# Sheet1.net
KiCad netlist of a schematic drawn in Altium Designer
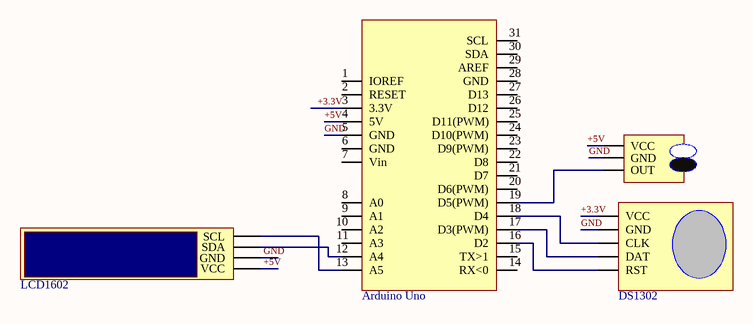
[diagram p0: Sheet1.SchDoc]

(export (version "E")
  (design (tool "Eeschema 10.0.6"))
  (components
    (comp (ref "Arduino") (value "Arduino Uno") (libsource (lib "Schlib1") (part "Arduino_C")))
    (comp (ref "LCD1602") (value "IIC1602") (libsource (lib "Schlib1") (part "IIC1602")))
    (comp (ref "rtc") (value "DS1302") (libsource (lib "Schlib1") (part "RTC时钟")))
    (comp (ref "红外避障") (value "红外避障1") (libsource (lib "Schlib1") (part "红外避障")))
  )
  (nets
    (net (code "1") (name "/+3.3V") (class "Default")
      (node (ref "Arduino") (pin "3") (pinfunction "3.3V_3") (pintype "passive"))
      (node (ref "rtc") (pin "241") (pinfunction "VCC_241") (pintype "passive"))
    )
    (net (code "2") (name "/+5V") (class "Default")
      (node (ref "Arduino") (pin "4") (pinfunction "5V_4") (pintype "passive"))
      (node (ref "LCD1602") (pin "192") (pinfunction "VCC_192") (pintype "passive"))
      (node (ref "红外避障") (pin "233") (pinfunction "VCC_233") (pintype "passive"))
    )
    (net (code "3") (name "/GND") (class "Default")
      (node (ref "Arduino") (pin "5") (pinfunction "GND_5") (pintype "passive"))
      (node (ref "LCD1602") (pin "193") (pinfunction "GND_193") (pintype "passive"))
      (node (ref "rtc") (pin "242") (pinfunction "GND_242") (pintype "passive"))
      (node (ref "红外避障") (pin "234") (pinfunction "GND_234") (pintype "passive"))
    )
    (net (code "4") (name "Net-(Arduino-A4)") (class "Default")
      (node (ref "Arduino") (pin "12") (pinfunction "A4_12") (pintype "passive"))
      (node (ref "LCD1602") (pin "194") (pinfunction "SDA_194") (pintype "passive"))
    )
    (net (code "5") (name "Net-(Arduino-A5)") (class "Default")
      (node (ref "Arduino") (pin "13") (pinfunction "A5_13") (pintype "passive"))
      (node (ref "LCD1602") (pin "195") (pinfunction "SCL_195") (pintype "passive"))
    )
    (net (code "6") (name "Net-(Arduino-D2)") (class "Default")
      (node (ref "Arduino") (pin "16") (pinfunction "D2_16") (pintype "passive"))
      (node (ref "rtc") (pin "245") (pinfunction "RST_245") (pintype "passive"))
    )
    (net (code "7") (name "Net-(Arduino-D3(PWM))") (class "Default")
      (node (ref "Arduino") (pin "17") (pinfunction "D3(PWM)_17") (pintype "passive"))
      (node (ref "rtc") (pin "244") (pinfunction "DAT_244") (pintype "passive"))
    )
    (net (code "8") (name "Net-(Arduino-D4)") (class "Default")
      (node (ref "Arduino") (pin "18") (pinfunction "D4_18") (pintype "passive"))
      (node (ref "rtc") (pin "243") (pinfunction "CLK_243") (pintype "passive"))
    )
    (net (code "9") (name "Net-(Arduino-D5(PWM))") (class "Default")
      (node (ref "Arduino") (pin "19") (pinfunction "D5(PWM)_19") (pintype "passive"))
      (node (ref "红外避障") (pin "235") (pinfunction "OUT_235") (pintype "passive"))
    )
    (net (code "10") (name "unconnected-(Arduino-A0-Pad8)") (class "Default")
      (node (ref "Arduino") (pin "8") (pinfunction "A0_8") (pintype "passive"))
    )
    (net (code "11") (name "unconnected-(Arduino-A1-Pad9)") (class "Default")
      (node (ref "Arduino") (pin "9") (pinfunction "A1_9") (pintype "passive"))
    )
    (net (code "12") (name "unconnected-(Arduino-A2-Pad10)") (class "Default")
      (node (ref "Arduino") (pin "10") (pinfunction "A2_10") (pintype "passive"))
    )
    (net (code "13") (name "unconnected-(Arduino-A3-Pad11)") (class "Default")
      (node (ref "Arduino") (pin "11") (pinfunction "A3_11") (pintype "passive"))
    )
    (net (code "14") (name "unconnected-(Arduino-AREF-Pad29)") (class "Default")
      (node (ref "Arduino") (pin "29") (pinfunction "AREF_29") (pintype "passive"))
    )
    (net (code "15") (name "unconnected-(Arduino-D6(PWM)-Pad20)") (class "Default")
      (node (ref "Arduino") (pin "20") (pinfunction "D6(PWM)_20") (pintype "passive"))
    )
    (net (code "16") (name "unconnected-(Arduino-D7-Pad21)") (class "Default")
      (node (ref "Arduino") (pin "21") (pinfunction "D7_21") (pintype "passive"))
    )
    (net (code "17") (name "unconnected-(Arduino-D8-Pad22)") (class "Default")
      (node (ref "Arduino") (pin "22") (pinfunction "D8_22") (pintype "passive"))
    )
    (net (code "18") (name "unconnected-(Arduino-D9(PWM)-Pad23)") (class "Default")
      (node (ref "Arduino") (pin "23") (pinfunction "D9(PWM)_23") (pintype "passive"))
    )
    (net (code "19") (name "unconnected-(Arduino-D10(PWM)-Pad24)") (class "Default")
      (node (ref "Arduino") (pin "24") (pinfunction "D10(PWM)_24") (pintype "passive"))
    )
    (net (code "20") (name "unconnected-(Arduino-D11(PWM)-Pad25)") (class "Default")
      (node (ref "Arduino") (pin "25") (pinfunction "D11(PWM)_25") (pintype "passive"))
    )
    (net (code "21") (name "unconnected-(Arduino-D12-Pad26)") (class "Default")
      (node (ref "Arduino") (pin "26") (pinfunction "D12_26") (pintype "passive"))
    )
    (net (code "22") (name "unconnected-(Arduino-D13-Pad27)") (class "Default")
      (node (ref "Arduino") (pin "27") (pinfunction "D13_27") (pintype "passive"))
    )
    (net (code "23") (name "unconnected-(Arduino-GND-Pad6)") (class "Default")
      (node (ref "Arduino") (pin "6") (pinfunction "GND_6") (pintype "passive"))
    )
    (net (code "24") (name "unconnected-(Arduino-GND-Pad28)") (class "Default")
      (node (ref "Arduino") (pin "28") (pinfunction "GND_28") (pintype "passive"))
    )
    (net (code "25") (name "unconnected-(Arduino-IOREF-Pad1)") (class "Default")
      (node (ref "Arduino") (pin "1") (pinfunction "IOREF_1") (pintype "passive"))
    )
    (net (code "26") (name "unconnected-(Arduino-RESET-Pad2)") (class "Default")
      (node (ref "Arduino") (pin "2") (pinfunction "RESET_2") (pintype "passive"))
    )
    (net (code "27") (name "unconnected-(Arduino-RX<0-Pad14)") (class "Default")
      (node (ref "Arduino") (pin "14") (pinfunction "RX<0_14") (pintype "passive"))
    )
    (net (code "28") (name "unconnected-(Arduino-SCL-Pad31)") (class "Default")
      (node (ref "Arduino") (pin "31") (pinfunction "SCL_31") (pintype "passive"))
    )
    (net (code "29") (name "unconnected-(Arduino-SDA-Pad30)") (class "Default")
      (node (ref "Arduino") (pin "30") (pinfunction "SDA_30") (pintype "passive"))
    )
    (net (code "30") (name "unconnected-(Arduino-TX>1-Pad15)") (class "Default")
      (node (ref "Arduino") (pin "15") (pinfunction "TX>1_15") (pintype "passive"))
    )
    (net (code "31") (name "unconnected-(Arduino-Vin-Pad7)") (class "Default")
      (node (ref "Arduino") (pin "7") (pinfunction "Vin_7") (pintype "passive"))
    )
  )
)
